# uCBoardBase.net
KiCad netlist of a schematic drawn in EAGLE
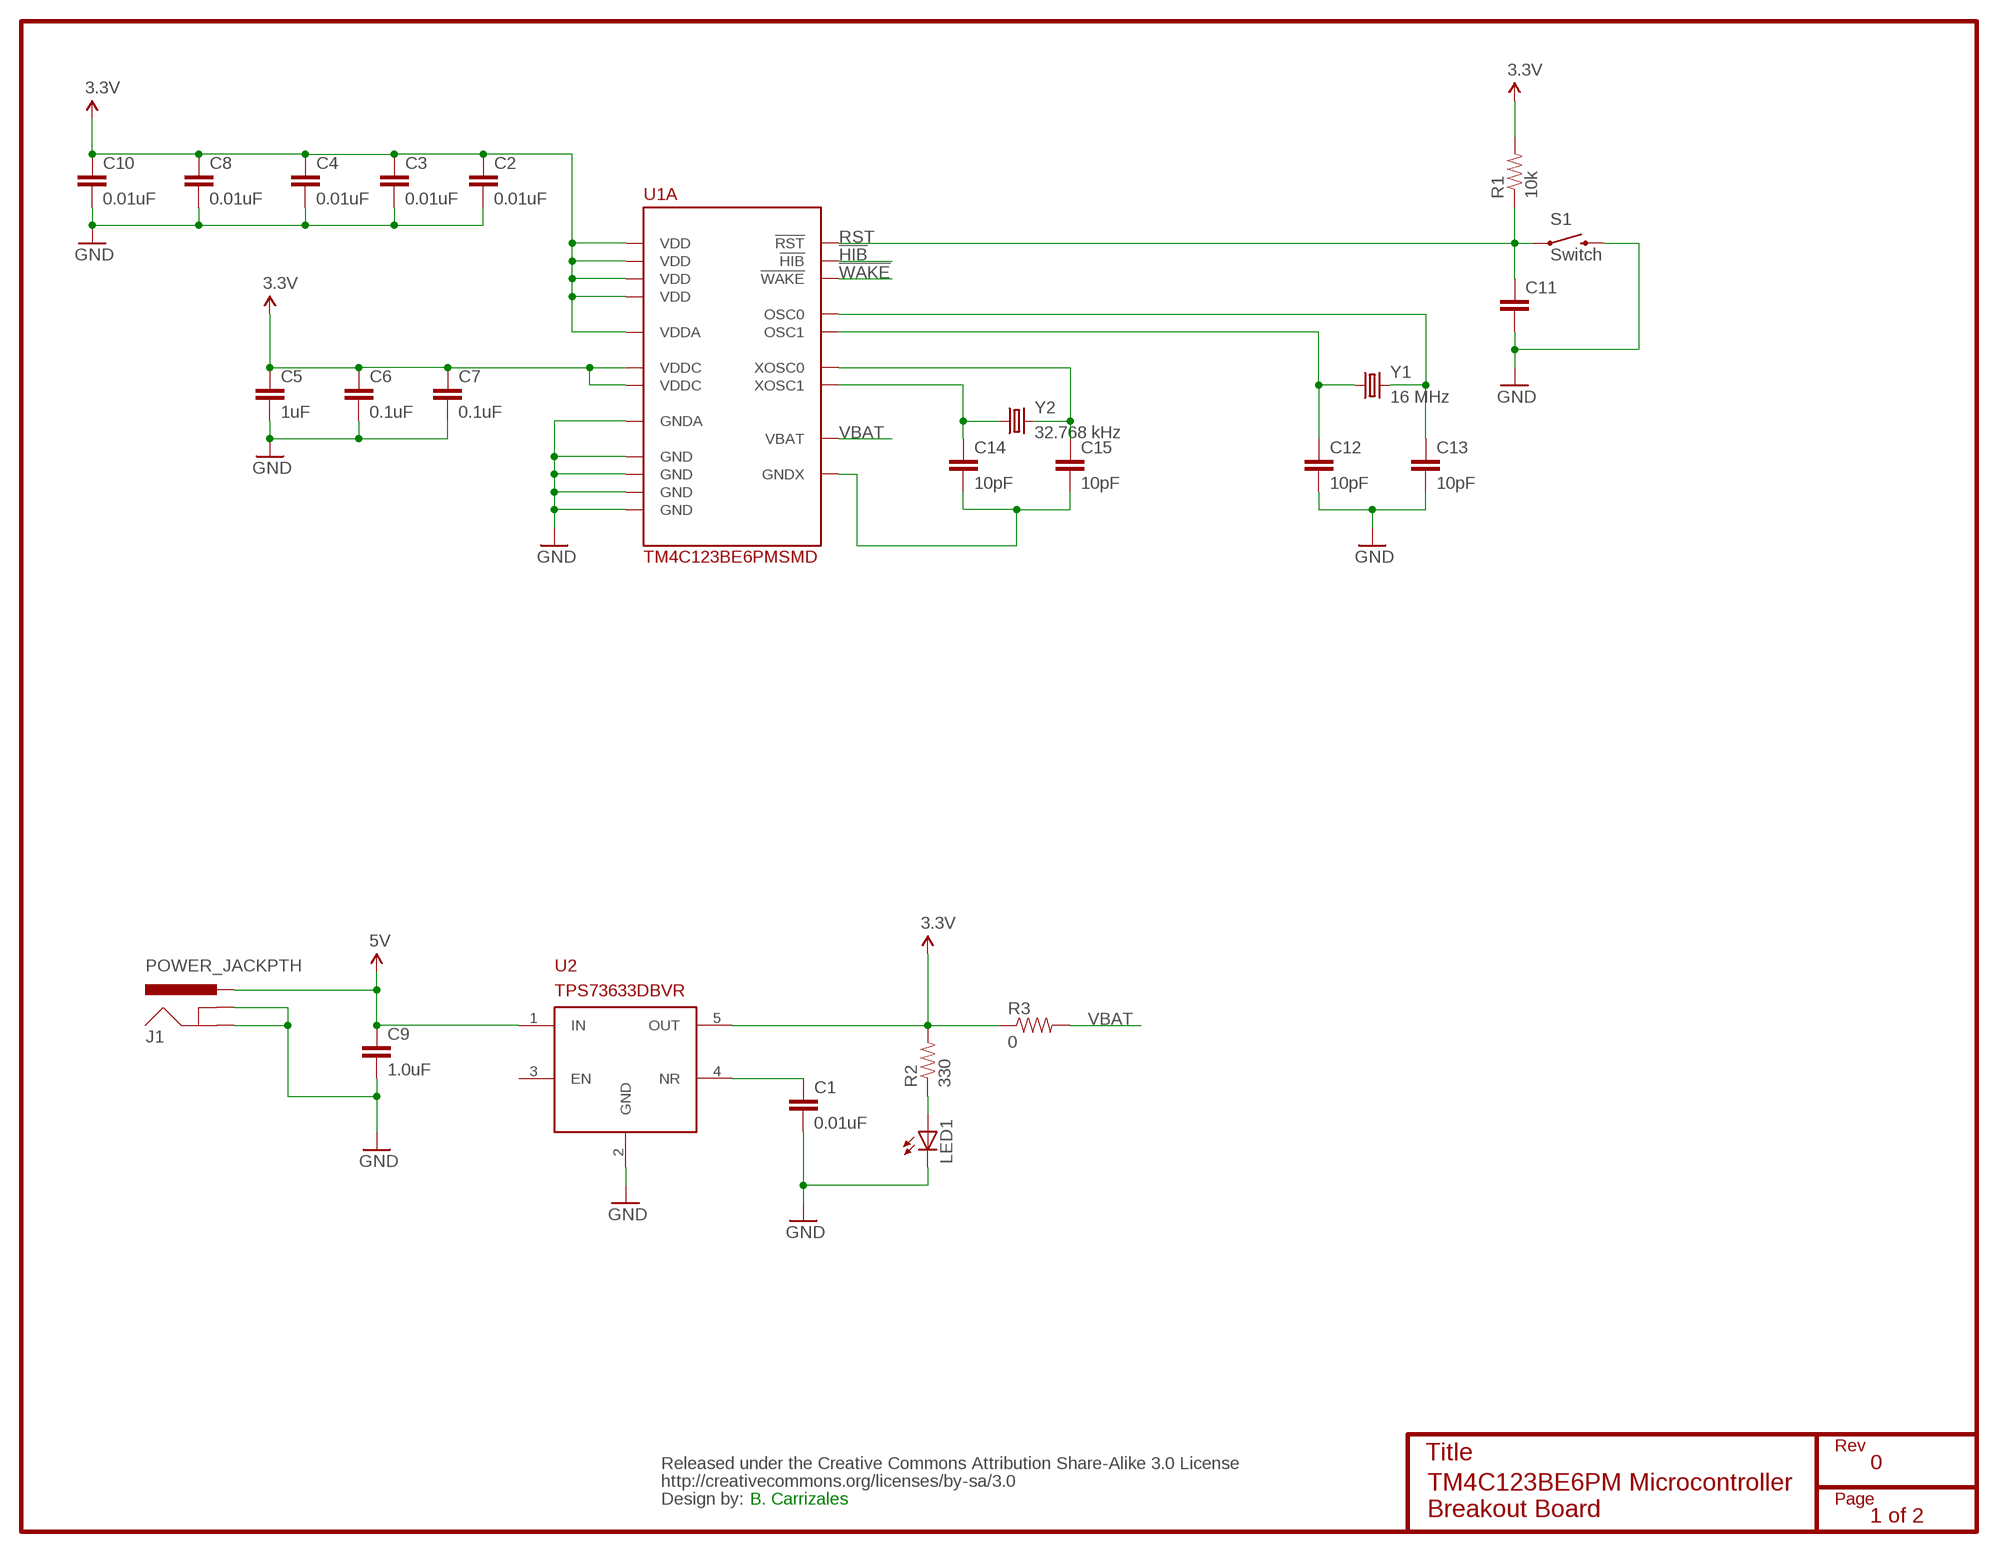
[diagram p0: schematic, sheet 1]
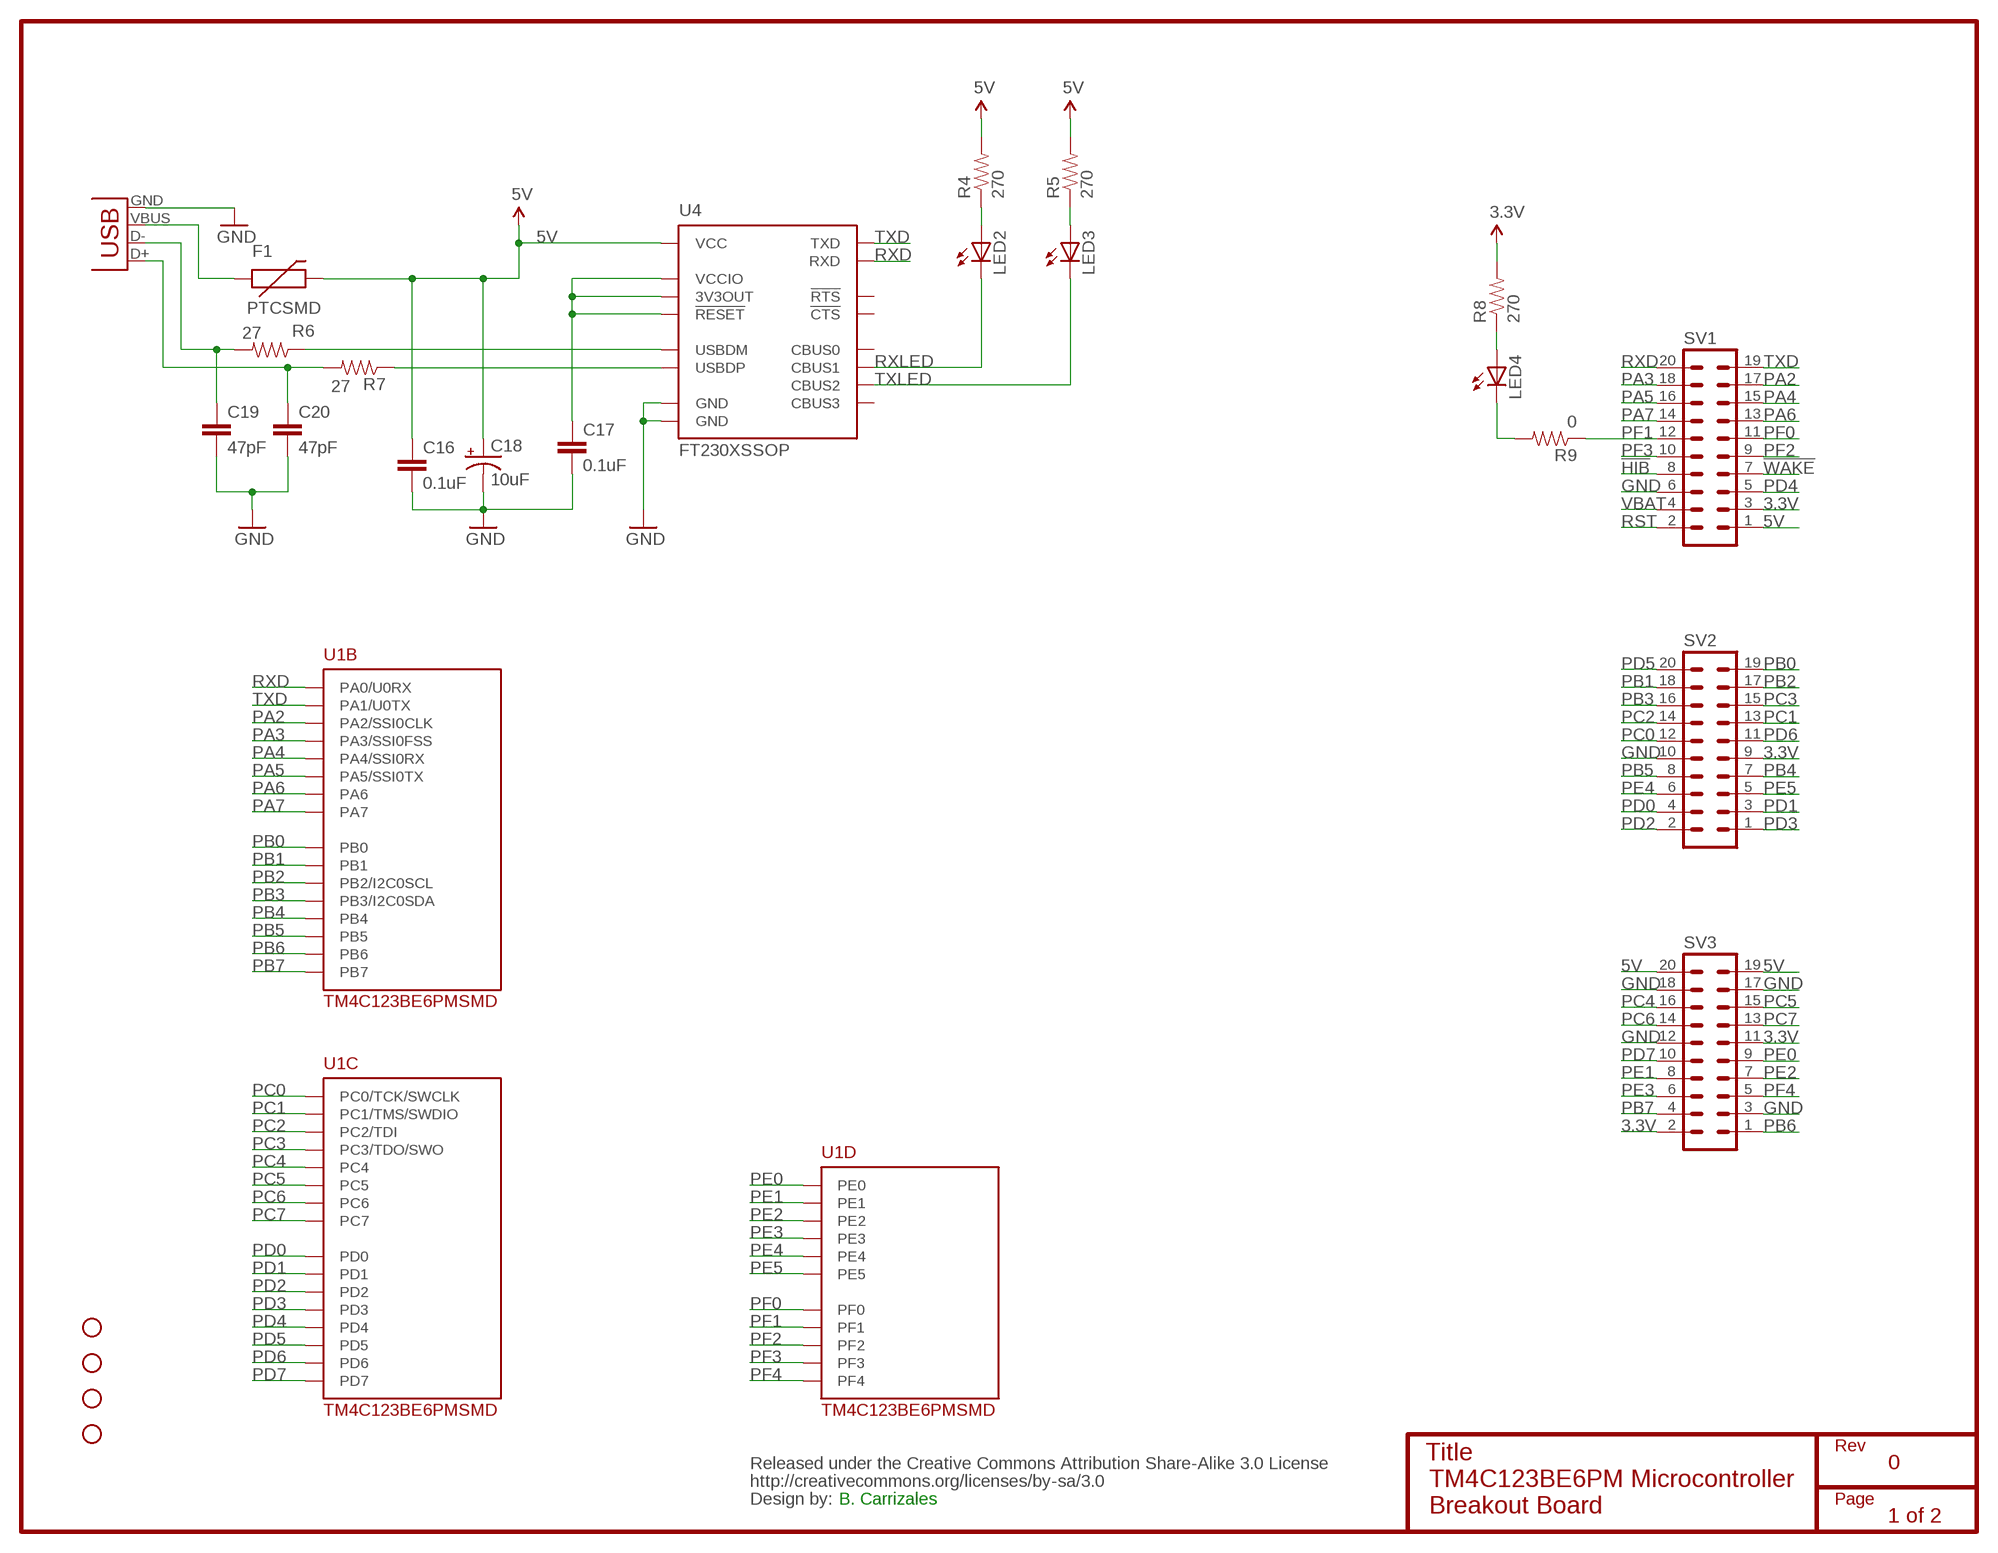
[diagram p1: schematic, sheet 2]

(export (version "E")
  (design (tool "Eeschema 10.0.6"))
  (components
    (comp (ref "C1")
      (value "0.01uF")
      (footprint "eagle-import:0603-CAP")
      (libsource (lib "eagle-import") (part "CAP0603-CAP"))
    )
    (comp (ref "C2")
      (value "0.01uF")
      (footprint "eagle-import:0603-CAP")
      (libsource (lib "eagle-import") (part "CAP0603-CAP"))
    )
    (comp (ref "C3")
      (value "0.01uF")
      (footprint "eagle-import:0603-CAP")
      (libsource (lib "eagle-import") (part "CAP0603-CAP"))
    )
    (comp (ref "C4")
      (value "0.01uF")
      (footprint "eagle-import:0603-CAP")
      (libsource (lib "eagle-import") (part "CAP0603-CAP"))
    )
    (comp (ref "C5")
      (value "1uF")
      (footprint "eagle-import:0603-CAP")
      (libsource (lib "eagle-import") (part "CAP0603-CAP"))
    )
    (comp (ref "C6")
      (value "0.1uF")
      (footprint "eagle-import:0603-CAP")
      (libsource (lib "eagle-import") (part "CAP0603-CAP"))
    )
    (comp (ref "C7")
      (value "0.1uF")
      (footprint "eagle-import:0603-CAP")
      (libsource (lib "eagle-import") (part "CAP0603-CAP"))
    )
    (comp (ref "C8")
      (value "0.01uF")
      (footprint "eagle-import:0603-CAP")
      (libsource (lib "eagle-import") (part "CAP0603-CAP"))
    )
    (comp (ref "C9")
      (value "1.0uF")
      (footprint "eagle-import:0603-CAP")
      (libsource (lib "eagle-import") (part "CAP0603-CAP"))
    )
    (comp (ref "C10")
      (value "0.01uF")
      (footprint "eagle-import:0603-CAP")
      (libsource (lib "eagle-import") (part "CAP0603-CAP"))
    )
    (comp (ref "C11")
      (value "CAP0603-CAP")
      (footprint "eagle-import:0603-CAP")
      (libsource (lib "eagle-import") (part "CAP0603-CAP"))
    )
    (comp (ref "C12")
      (value "10pF")
      (footprint "eagle-import:0603-CAP")
      (libsource (lib "eagle-import") (part "CAP0603-CAP"))
    )
    (comp (ref "C13")
      (value "10pF")
      (footprint "eagle-import:0603-CAP")
      (libsource (lib "eagle-import") (part "CAP0603-CAP"))
    )
    (comp (ref "C14")
      (value "10pF")
      (footprint "eagle-import:0603-CAP")
      (libsource (lib "eagle-import") (part "CAP0603-CAP"))
    )
    (comp (ref "C15")
      (value "10pF")
      (footprint "eagle-import:0603-CAP")
      (libsource (lib "eagle-import") (part "CAP0603-CAP"))
    )
    (comp (ref "CC_TEXT1")
      (value "CREATIVE_COMMONS")
      (footprint "eagle-import:CREATIVE_COMMONS")
      (libsource (lib "eagle-import") (part "CREATIVE_COMMONS"))
    )
    (comp (ref "J1")
      (value "POWER_JACKPTH")
      (footprint "eagle-import:POWER_JACK_PTH")
      (libsource (lib "eagle-import") (part "POWER_JACKPTH"))
    )
    (comp (ref "LED1")
      (value "LED1206")
      (footprint "eagle-import:LED-1206")
      (libsource (lib "eagle-import") (part "LED1206"))
    )
    (comp (ref "R1")
      (value "10k")
      (footprint "eagle-import:0603-RES")
      (libsource (lib "eagle-import") (part "RESISTOR0603-RES"))
    )
    (comp (ref "R2")
      (value "330")
      (footprint "eagle-import:0603-RES")
      (libsource (lib "eagle-import") (part "RESISTOR0603-RES"))
    )
    (comp (ref "R3")
      (value "0")
      (footprint "eagle-import:0603-RES")
      (libsource (lib "eagle-import") (part "RESISTOR0603-RES"))
    )
    (comp (ref "S1")
      (value "Switch")
      (footprint "eagle-import:TACTILE-SWITCH-1101NE")
      (libsource (lib "eagle-import") (part "SWITCH-MOMENTARY-2-SMD-1101NE"))
    )
    (comp (ref "U1")
      (value "TM4C123BE6PMSMD")
      (footprint "eagle-import:64LQFP")
      (fields (field (name "DIGIKEYPART#") "296-35834-ND"))
      (libsource (lib "eagle-import") (part "TM4C123BE6PMSMD"))
    )
    (comp (ref "U2")
      (value "TPS73633DBVR")
      (footprint "eagle-import:SOT23-DBV")
      (libsource (lib "eagle-import") (part "TPS73633DBVR"))
    )
    (comp (ref "Y1")
      (value "16 MHz")
      (footprint "eagle-import:HC49US")
      (libsource (lib "eagle-import") (part "CRYSTALHC49US"))
    )
    (comp (ref "Y2")
      (value "32.768 kHz")
      (footprint "eagle-import:TC26H")
      (libsource (lib "eagle-import") (part "CRYSTALTC26H"))
    )
    (comp (ref "C16")
      (value "0.1uF")
      (footprint "eagle-import:0603-CAP")
      (libsource (lib "eagle-import") (part "CAP0603-CAP"))
    )
    (comp (ref "C17")
      (value "0.1uF")
      (footprint "eagle-import:0603-CAP")
      (libsource (lib "eagle-import") (part "CAP0603-CAP"))
    )
    (comp (ref "C18")
      (value "10uF")
      (footprint "eagle-import:EIA3216-KIT")
      (libsource (lib "eagle-import") (part "CAP_POL1206-KIT"))
    )
    (comp (ref "C19")
      (value "47pF")
      (footprint "eagle-import:0603-CAP")
      (libsource (lib "eagle-import") (part "CAP0603-CAP"))
    )
    (comp (ref "C20")
      (value "47pF")
      (footprint "eagle-import:0603-CAP")
      (libsource (lib "eagle-import") (part "CAP0603-CAP"))
    )
    (comp (ref "CC_TEXT2")
      (value "CREATIVE_COMMONS")
      (footprint "eagle-import:CREATIVE_COMMONS")
      (libsource (lib "eagle-import") (part "CREATIVE_COMMONS"))
    )
    (comp (ref "F1")
      (value "PTCSMD")
      (footprint "eagle-import:PTC-1206")
      (libsource (lib "eagle-import") (part "PTCSMD"))
    )
    (comp (ref "JP2")
      (value "USBSMD")
      (footprint "eagle-import:USB-MINIB")
      (libsource (lib "eagle-import") (part "USBSMD"))
    )
    (comp (ref "LED2")
      (value "LED0603")
      (footprint "eagle-import:LED-0603")
      (libsource (lib "eagle-import") (part "LED0603"))
    )
    (comp (ref "LED3")
      (value "LED0603")
      (footprint "eagle-import:LED-0603")
      (libsource (lib "eagle-import") (part "LED0603"))
    )
    (comp (ref "LED4")
      (value "LED0603")
      (footprint "eagle-import:LED-0603")
      (libsource (lib "eagle-import") (part "LED0603"))
    )
    (comp (ref "R4")
      (value "270")
      (footprint "eagle-import:0603-RES")
      (libsource (lib "eagle-import") (part "RESISTOR0603-RES"))
    )
    (comp (ref "R5")
      (value "270")
      (footprint "eagle-import:0603-RES")
      (libsource (lib "eagle-import") (part "RESISTOR0603-RES"))
    )
    (comp (ref "R6")
      (value "27")
      (footprint "eagle-import:0603-RES")
      (libsource (lib "eagle-import") (part "RESISTOR0603-RES"))
    )
    (comp (ref "R7")
      (value "27")
      (footprint "eagle-import:0603-RES")
      (libsource (lib "eagle-import") (part "RESISTOR0603-RES"))
    )
    (comp (ref "R8")
      (value "270")
      (footprint "eagle-import:0603-RES")
      (libsource (lib "eagle-import") (part "RESISTOR0603-RES"))
    )
    (comp (ref "R9")
      (value "0")
      (footprint "eagle-import:0603-RES")
      (libsource (lib "eagle-import") (part "RESISTOR0603-RES"))
    )
    (comp (ref "STANDOFF1")
      (value "STAND-OFF")
      (footprint "eagle-import:STAND-OFF")
      (libsource (lib "eagle-import") (part "STAND-OFF"))
    )
    (comp (ref "STANDOFF2")
      (value "STAND-OFF")
      (footprint "eagle-import:STAND-OFF")
      (libsource (lib "eagle-import") (part "STAND-OFF"))
    )
    (comp (ref "STANDOFF3")
      (value "STAND-OFF")
      (footprint "eagle-import:STAND-OFF")
      (libsource (lib "eagle-import") (part "STAND-OFF"))
    )
    (comp (ref "STANDOFF4")
      (value "STAND-OFF")
      (footprint "eagle-import:STAND-OFF")
      (libsource (lib "eagle-import") (part "STAND-OFF"))
    )
    (comp (ref "SV1")
      (value "MA10-2")
      (footprint "eagle-import:MA10-2")
      (libsource (lib "eagle-import") (part "MA10-2"))
    )
    (comp (ref "SV2")
      (value "MA10-2")
      (footprint "eagle-import:MA10-2")
      (libsource (lib "eagle-import") (part "MA10-2"))
    )
    (comp (ref "SV3")
      (value "MA10-2")
      (footprint "eagle-import:MA10-2")
      (libsource (lib "eagle-import") (part "MA10-2"))
    )
    (comp (ref "U4")
      (value "FT230XSSOP")
      (footprint "eagle-import:SSOP16")
      (libsource (lib "eagle-import") (part "FT230XSSOP"))
    )
  )
  (nets
    (net (code "1") (name "3.3V") (class "Default")
      (node (ref "C10") (pin "1") (pinfunction "1_1") (pintype "passive"))
      (node (ref "C2") (pin "1") (pinfunction "1_1") (pintype "passive"))
      (node (ref "C3") (pin "1") (pinfunction "1_1") (pintype "passive"))
      (node (ref "C4") (pin "1") (pinfunction "1_1") (pintype "passive"))
      (node (ref "C5") (pin "1") (pinfunction "1_1") (pintype "passive"))
      (node (ref "C6") (pin "1") (pinfunction "1_1") (pintype "passive"))
      (node (ref "C7") (pin "1") (pinfunction "1_1") (pintype "passive"))
      (node (ref "C8") (pin "1") (pinfunction "1_1") (pintype "passive"))
      (node (ref "R1") (pin "2") (pinfunction "2_2") (pintype "passive"))
      (node (ref "R2") (pin "2") (pinfunction "2_2") (pintype "passive"))
      (node (ref "R3") (pin "1") (pinfunction "1_1") (pintype "passive"))
      (node (ref "R8") (pin "2") (pinfunction "2_2") (pintype "passive"))
      (node (ref "SV1") (pin "3") (pinfunction "3_3") (pintype "passive"))
      (node (ref "SV2") (pin "9") (pinfunction "9_9") (pintype "passive"))
      (node (ref "SV3") (pin "11") (pinfunction "11_11") (pintype "passive"))
      (node (ref "SV3") (pin "2") (pinfunction "2_2") (pintype "passive"))
      (node (ref "U1") (pin "11") (pinfunction "VDD_11") (pintype "power_in"))
      (node (ref "U1") (pin "2") (pinfunction "VDDA_2") (pintype "power_in"))
      (node (ref "U1") (pin "25") (pinfunction "VDDC_25") (pintype "power_in"))
      (node (ref "U1") (pin "26") (pinfunction "VDD_26") (pintype "power_in"))
      (node (ref "U1") (pin "42") (pinfunction "VDD_42") (pintype "power_in"))
      (node (ref "U1") (pin "54") (pinfunction "VDD_54") (pintype "power_in"))
      (node (ref "U1") (pin "56") (pinfunction "VDDC_56") (pintype "power_in"))
      (node (ref "U2") (pin "5") (pinfunction "OUT_5") (pintype "bidirectional"))
    )
    (net (code "2") (name "5V") (class "Default")
      (node (ref "C16") (pin "1") (pinfunction "1_1") (pintype "passive"))
      (node (ref "C18") (pin "A") (pinfunction "+_A") (pintype "passive"))
      (node (ref "C9") (pin "1") (pinfunction "1_1") (pintype "passive"))
      (node (ref "F1") (pin "2") (pinfunction "2_2") (pintype "bidirectional"))
      (node (ref "J1") (pin "PWR") (pinfunction "PWR_PWR") (pintype "bidirectional"))
      (node (ref "R4") (pin "2") (pinfunction "2_2") (pintype "passive"))
      (node (ref "R5") (pin "2") (pinfunction "2_2") (pintype "passive"))
      (node (ref "SV1") (pin "1") (pinfunction "1_1") (pintype "passive"))
      (node (ref "SV3") (pin "19") (pinfunction "19_19") (pintype "passive"))
      (node (ref "SV3") (pin "20") (pinfunction "20_20") (pintype "passive"))
      (node (ref "U2") (pin "1") (pinfunction "IN_1") (pintype "bidirectional"))
      (node (ref "U4") (pin "12") (pinfunction "VCC_12") (pintype "power_in"))
    )
    (net (code "3") (name "GND") (class "Default")
      (node (ref "C1") (pin "2") (pinfunction "2_2") (pintype "passive"))
      (node (ref "C10") (pin "2") (pinfunction "2_2") (pintype "passive"))
      (node (ref "C11") (pin "2") (pinfunction "2_2") (pintype "passive"))
      (node (ref "C12") (pin "2") (pinfunction "2_2") (pintype "passive"))
      (node (ref "C13") (pin "2") (pinfunction "2_2") (pintype "passive"))
      (node (ref "C16") (pin "2") (pinfunction "2_2") (pintype "passive"))
      (node (ref "C17") (pin "2") (pinfunction "2_2") (pintype "passive"))
      (node (ref "C18") (pin "C") (pinfunction "-_C") (pintype "passive"))
      (node (ref "C19") (pin "2") (pinfunction "2_2") (pintype "passive"))
      (node (ref "C2") (pin "2") (pinfunction "2_2") (pintype "passive"))
      (node (ref "C20") (pin "2") (pinfunction "2_2") (pintype "passive"))
      (node (ref "C3") (pin "2") (pinfunction "2_2") (pintype "passive"))
      (node (ref "C4") (pin "2") (pinfunction "2_2") (pintype "passive"))
      (node (ref "C5") (pin "2") (pinfunction "2_2") (pintype "passive"))
      (node (ref "C6") (pin "2") (pinfunction "2_2") (pintype "passive"))
      (node (ref "C7") (pin "2") (pinfunction "2_2") (pintype "passive"))
      (node (ref "C8") (pin "2") (pinfunction "2_2") (pintype "passive"))
      (node (ref "C9") (pin "2") (pinfunction "2_2") (pintype "passive"))
      (node (ref "J1") (pin "GND") (pinfunction "GND_GND") (pintype "bidirectional"))
      (node (ref "J1") (pin "GNDBREAK") (pinfunction "GNDBREAK_GNDBREAK") (pintype "bidirectional"))
      (node (ref "JP2") (pin "GND") (pinfunction "GND_GND") (pintype "bidirectional"))
      (node (ref "LED1") (pin "C") (pinfunction "C_C") (pintype "passive"))
      (node (ref "S1") (pin "P$2") (pinfunction "2_P$2") (pintype "passive"))
      (node (ref "SV1") (pin "6") (pinfunction "6_6") (pintype "passive"))
      (node (ref "SV2") (pin "10") (pinfunction "10_10") (pintype "passive"))
      (node (ref "SV3") (pin "12") (pinfunction "12_12") (pintype "passive"))
      (node (ref "SV3") (pin "17") (pinfunction "17_17") (pintype "passive"))
      (node (ref "SV3") (pin "18") (pinfunction "18_18") (pintype "passive"))
      (node (ref "SV3") (pin "3") (pinfunction "3_3") (pintype "passive"))
      (node (ref "U1") (pin "12") (pinfunction "GND_12") (pintype "power_in"))
      (node (ref "U1") (pin "27") (pinfunction "GND_27") (pintype "power_in"))
      (node (ref "U1") (pin "3") (pinfunction "GNDA_3") (pintype "power_in"))
      (node (ref "U1") (pin "39") (pinfunction "GND_39") (pintype "power_in"))
      (node (ref "U1") (pin "55") (pinfunction "GND_55") (pintype "power_in"))
      (node (ref "U2") (pin "2") (pinfunction "GND_2") (pintype "bidirectional"))
      (node (ref "U4") (pin "13") (pinfunction "GND_13") (pintype "power_in"))
      (node (ref "U4") (pin "5") (pinfunction "GND_5") (pintype "power_in"))
    )
    (net (code "4") (name "Net-(C19-Pad1)") (class "Default")
      (node (ref "C19") (pin "1") (pinfunction "1_1") (pintype "passive"))
      (node (ref "JP2") (pin "D-") (pinfunction "D-_D-") (pintype "bidirectional"))
      (node (ref "R6") (pin "2") (pinfunction "2_2") (pintype "passive"))
    )
    (net (code "5") (name "Net-(C20-Pad1)") (class "Default")
      (node (ref "C20") (pin "1") (pinfunction "1_1") (pintype "passive"))
      (node (ref "JP2") (pin "D+") (pinfunction "D+_D+") (pintype "bidirectional"))
      (node (ref "R7") (pin "2") (pinfunction "2_2") (pintype "passive"))
    )
    (net (code "6") (name "Net-(F1-Pad1)") (class "Default")
      (node (ref "F1") (pin "1") (pinfunction "1_1") (pintype "bidirectional"))
      (node (ref "JP2") (pin "VBUS") (pinfunction "VBUS_VBUS") (pintype "bidirectional"))
    )
    (net (code "7") (name "Net-(LED1-PadA)") (class "Default")
      (node (ref "LED1") (pin "A") (pinfunction "A_A") (pintype "passive"))
      (node (ref "R2") (pin "1") (pinfunction "1_1") (pintype "passive"))
    )
    (net (code "8") (name "Net-(LED2-PadA)") (class "Default")
      (node (ref "LED2") (pin "A") (pinfunction "A_A") (pintype "passive"))
      (node (ref "R4") (pin "1") (pinfunction "1_1") (pintype "passive"))
    )
    (net (code "9") (name "Net-(LED3-PadA)") (class "Default")
      (node (ref "LED3") (pin "A") (pinfunction "A_A") (pintype "passive"))
      (node (ref "R5") (pin "1") (pinfunction "1_1") (pintype "passive"))
    )
    (net (code "10") (name "Net-(LED4-PadA)") (class "Default")
      (node (ref "LED4") (pin "A") (pinfunction "A_A") (pintype "passive"))
      (node (ref "R8") (pin "1") (pinfunction "1_1") (pintype "passive"))
    )
    (net (code "11") (name "Net-(LED4-PadC)") (class "Default")
      (node (ref "LED4") (pin "C") (pinfunction "C_C") (pintype "passive"))
      (node (ref "R9") (pin "2") (pinfunction "2_2") (pintype "passive"))
    )
    (net (code "12") (name "Net-(U1A-GNDX)") (class "Default")
      (node (ref "C14") (pin "2") (pinfunction "2_2") (pintype "passive"))
      (node (ref "C15") (pin "2") (pinfunction "2_2") (pintype "passive"))
      (node (ref "U1") (pin "35") (pinfunction "GNDX_35") (pintype "power_in"))
    )
    (net (code "13") (name "Net-(U1A-OSC0)") (class "Default")
      (node (ref "C13") (pin "1") (pinfunction "1_1") (pintype "passive"))
      (node (ref "U1") (pin "40") (pinfunction "OSC0_40") (pintype "input"))
      (node (ref "Y1") (pin "2") (pinfunction "2_2") (pintype "passive"))
    )
    (net (code "14") (name "Net-(U1A-OSC1)") (class "Default")
      (node (ref "C12") (pin "1") (pinfunction "1_1") (pintype "passive"))
      (node (ref "U1") (pin "41") (pinfunction "OSC1_41") (pintype "output"))
      (node (ref "Y1") (pin "1") (pinfunction "1_1") (pintype "passive"))
    )
    (net (code "15") (name "Net-(U1A-XOSC0)") (class "Default")
      (node (ref "C15") (pin "1") (pinfunction "1_1") (pintype "passive"))
      (node (ref "U1") (pin "34") (pinfunction "XOSC0_34") (pintype "input"))
      (node (ref "Y2") (pin "2") (pinfunction "2_2") (pintype "passive"))
    )
    (net (code "16") (name "Net-(U1A-XOSC1)") (class "Default")
      (node (ref "C14") (pin "1") (pinfunction "1_1") (pintype "passive"))
      (node (ref "U1") (pin "36") (pinfunction "XOSC1_36") (pintype "output"))
      (node (ref "Y2") (pin "1") (pinfunction "1_1") (pintype "passive"))
    )
    (net (code "17") (name "Net-(U2-NR)") (class "Default")
      (node (ref "C1") (pin "1") (pinfunction "1_1") (pintype "passive"))
      (node (ref "U2") (pin "4") (pinfunction "NR_4") (pintype "bidirectional"))
    )
    (net (code "18") (name "Net-(U4-3V3OUT)") (class "Default")
      (node (ref "C17") (pin "1") (pinfunction "1_1") (pintype "passive"))
      (node (ref "U4") (pin "10") (pinfunction "3V3OUT_10") (pintype "power_in"))
      (node (ref "U4") (pin "11") (pinfunction "~{RESET}_11") (pintype "input"))
      (node (ref "U4") (pin "3") (pinfunction "VCCIO_3") (pintype "power_in"))
    )
    (net (code "19") (name "Net-(U4-USBDM)") (class "Default")
      (node (ref "R6") (pin "1") (pinfunction "1_1") (pintype "passive"))
      (node (ref "U4") (pin "9") (pinfunction "USBDM_9") (pintype "input"))
    )
    (net (code "20") (name "Net-(U4-USBDP)") (class "Default")
      (node (ref "R7") (pin "1") (pinfunction "1_1") (pintype "passive"))
      (node (ref "U4") (pin "8") (pinfunction "USBDP_8") (pintype "input"))
    )
    (net (code "21") (name "PA2") (class "Default")
      (node (ref "SV1") (pin "17") (pinfunction "17_17") (pintype "passive"))
      (node (ref "U1") (pin "19") (pinfunction "PA2/SSI0CLK_19") (pintype "bidirectional"))
    )
    (net (code "22") (name "PA3") (class "Default")
      (node (ref "SV1") (pin "18") (pinfunction "18_18") (pintype "passive"))
      (node (ref "U1") (pin "20") (pinfunction "PA3/SSI0FSS_20") (pintype "bidirectional"))
    )
    (net (code "23") (name "PA4") (class "Default")
      (node (ref "SV1") (pin "15") (pinfunction "15_15") (pintype "passive"))
      (node (ref "U1") (pin "21") (pinfunction "PA4/SSI0RX_21") (pintype "bidirectional"))
    )
    (net (code "24") (name "PA5") (class "Default")
      (node (ref "SV1") (pin "16") (pinfunction "16_16") (pintype "passive"))
      (node (ref "U1") (pin "22") (pinfunction "PA5/SSI0TX_22") (pintype "bidirectional"))
    )
    (net (code "25") (name "PA6") (class "Default")
      (node (ref "SV1") (pin "13") (pinfunction "13_13") (pintype "passive"))
      (node (ref "U1") (pin "23") (pinfunction "PA6_23") (pintype "bidirectional"))
    )
    (net (code "26") (name "PA7") (class "Default")
      (node (ref "SV1") (pin "14") (pinfunction "14_14") (pintype "passive"))
      (node (ref "U1") (pin "24") (pinfunction "PA7_24") (pintype "bidirectional"))
    )
    (net (code "27") (name "PB0") (class "Default")
      (node (ref "SV2") (pin "19") (pinfunction "19_19") (pintype "passive"))
      (node (ref "U1") (pin "45") (pinfunction "PB0_45") (pintype "bidirectional"))
    )
    (net (code "28") (name "PB1") (class "Default")
      (node (ref "SV2") (pin "18") (pinfunction "18_18") (pintype "passive"))
      (node (ref "U1") (pin "46") (pinfunction "PB1_46") (pintype "bidirectional"))
    )
    (net (code "29") (name "PB2") (class "Default")
      (node (ref "SV2") (pin "17") (pinfunction "17_17") (pintype "passive"))
      (node (ref "U1") (pin "47") (pinfunction "PB2/I2C0SCL_47") (pintype "bidirectional"))
    )
    (net (code "30") (name "PB3") (class "Default")
      (node (ref "SV2") (pin "16") (pinfunction "16_16") (pintype "passive"))
      (node (ref "U1") (pin "48") (pinfunction "PB3/I2C0SDA_48") (pintype "bidirectional"))
    )
    (net (code "31") (name "PB4") (class "Default")
      (node (ref "SV2") (pin "7") (pinfunction "7_7") (pintype "passive"))
      (node (ref "U1") (pin "58") (pinfunction "PB4_58") (pintype "bidirectional"))
    )
    (net (code "32") (name "PB5") (class "Default")
      (node (ref "SV2") (pin "8") (pinfunction "8_8") (pintype "passive"))
      (node (ref "U1") (pin "57") (pinfunction "PB5_57") (pintype "bidirectional"))
    )
    (net (code "33") (name "PB6") (class "Default")
      (node (ref "SV3") (pin "1") (pinfunction "1_1") (pintype "passive"))
      (node (ref "U1") (pin "1") (pinfunction "PB6_1") (pintype "bidirectional"))
    )
    (net (code "34") (name "PB7") (class "Default")
      (node (ref "SV3") (pin "4") (pinfunction "4_4") (pintype "passive"))
      (node (ref "U1") (pin "4") (pinfunction "PB7_4") (pintype "bidirectional"))
    )
    (net (code "35") (name "PC0") (class "Default")
      (node (ref "SV2") (pin "12") (pinfunction "12_12") (pintype "passive"))
      (node (ref "U1") (pin "52") (pinfunction "PC0/TCK/SWCLK_52") (pintype "bidirectional"))
    )
    (net (code "36") (name "PC1") (class "Default")
      (node (ref "SV2") (pin "13") (pinfunction "13_13") (pintype "passive"))
      (node (ref "U1") (pin "51") (pinfunction "PC1/TMS/SWDIO_51") (pintype "bidirectional"))
    )
    (net (code "37") (name "PC2") (class "Default")
      (node (ref "SV2") (pin "14") (pinfunction "14_14") (pintype "passive"))
      (node (ref "U1") (pin "50") (pinfunction "PC2/TDI_50") (pintype "bidirectional"))
    )
    (net (code "38") (name "PC3") (class "Default")
      (node (ref "SV2") (pin "15") (pinfunction "15_15") (pintype "passive"))
      (node (ref "U1") (pin "49") (pinfunction "PC3/TDO/SWO_49") (pintype "bidirectional"))
    )
    (net (code "39") (name "PC4") (class "Default")
      (node (ref "SV3") (pin "16") (pinfunction "16_16") (pintype "passive"))
      (node (ref "U1") (pin "16") (pinfunction "PC4_16") (pintype "bidirectional"))
    )
    (net (code "40") (name "PC5") (class "Default")
      (node (ref "SV3") (pin "15") (pinfunction "15_15") (pintype "passive"))
      (node (ref "U1") (pin "15") (pinfunction "PC5_15") (pintype "bidirectional"))
    )
    (net (code "41") (name "PC6") (class "Default")
      (node (ref "SV3") (pin "14") (pinfunction "14_14") (pintype "passive"))
      (node (ref "U1") (pin "14") (pinfunction "PC6_14") (pintype "bidirectional"))
    )
    (net (code "42") (name "PC7") (class "Default")
      (node (ref "SV3") (pin "13") (pinfunction "13_13") (pintype "passive"))
      (node (ref "U1") (pin "13") (pinfunction "PC7_13") (pintype "bidirectional"))
    )
    (net (code "43") (name "PD0") (class "Default")
      (node (ref "SV2") (pin "4") (pinfunction "4_4") (pintype "passive"))
      (node (ref "U1") (pin "61") (pinfunction "PD0_61") (pintype "bidirectional"))
    )
    (net (code "44") (name "PD1") (class "Default")
      (node (ref "SV2") (pin "3") (pinfunction "3_3") (pintype "passive"))
      (node (ref "U1") (pin "62") (pinfunction "PD1_62") (pintype "bidirectional"))
    )
    (net (code "45") (name "PD2") (class "Default")
      (node (ref "SV2") (pin "2") (pinfunction "2_2") (pintype "passive"))
      (node (ref "U1") (pin "63") (pinfunction "PD2_63") (pintype "bidirectional"))
    )
    (net (code "46") (name "PD3") (class "Default")
      (node (ref "SV2") (pin "1") (pinfunction "1_1") (pintype "passive"))
      (node (ref "U1") (pin "64") (pinfunction "PD3_64") (pintype "bidirectional"))
    )
    (net (code "47") (name "PD4") (class "Default")
      (node (ref "SV1") (pin "5") (pinfunction "5_5") (pintype "passive"))
      (node (ref "U1") (pin "43") (pinfunction "PD4_43") (pintype "bidirectional"))
    )
    (net (code "48") (name "PD5") (class "Default")
      (node (ref "SV2") (pin "20") (pinfunction "20_20") (pintype "passive"))
      (node (ref "U1") (pin "44") (pinfunction "PD5_44") (pintype "bidirectional"))
    )
    (net (code "49") (name "PD6") (class "Default")
      (node (ref "SV2") (pin "11") (pinfunction "11_11") (pintype "passive"))
      (node (ref "U1") (pin "53") (pinfunction "PD6_53") (pintype "bidirectional"))
    )
    (net (code "50") (name "PD7") (class "Default")
      (node (ref "SV3") (pin "10") (pinfunction "10_10") (pintype "passive"))
      (node (ref "U1") (pin "10") (pinfunction "PD7_10") (pintype "bidirectional"))
    )
    (net (code "51") (name "PE0") (class "Default")
      (node (ref "SV3") (pin "9") (pinfunction "9_9") (pintype "passive"))
      (node (ref "U1") (pin "9") (pinfunction "PE0_9") (pintype "bidirectional"))
    )
    (net (code "52") (name "PE1") (class "Default")
      (node (ref "SV3") (pin "8") (pinfunction "8_8") (pintype "passive"))
      (node (ref "U1") (pin "8") (pinfunction "PE1_8") (pintype "bidirectional"))
    )
    (net (code "53") (name "PE2") (class "Default")
      (node (ref "SV3") (pin "7") (pinfunction "7_7") (pintype "passive"))
      (node (ref "U1") (pin "7") (pinfunction "PE2_7") (pintype "bidirectional"))
    )
    (net (code "54") (name "PE3") (class "Default")
      (node (ref "SV3") (pin "6") (pinfunction "6_6") (pintype "passive"))
      (node (ref "U1") (pin "6") (pinfunction "PE3_6") (pintype "bidirectional"))
    )
    (net (code "55") (name "PE4") (class "Default")
      (node (ref "SV2") (pin "6") (pinfunction "6_6") (pintype "passive"))
      (node (ref "U1") (pin "59") (pinfunction "PE4_59") (pintype "bidirectional"))
    )
    (net (code "56") (name "PE5") (class "Default")
      (node (ref "SV2") (pin "5") (pinfunction "5_5") (pintype "passive"))
      (node (ref "U1") (pin "60") (pinfunction "PE5_60") (pintype "bidirectional"))
    )
    (net (code "57") (name "PF0") (class "Default")
      (node (ref "SV1") (pin "11") (pinfunction "11_11") (pintype "passive"))
      (node (ref "U1") (pin "28") (pinfunction "PF0_28") (pintype "bidirectional"))
    )
    (net (code "58") (name "PF1") (class "Default")
      (node (ref "R9") (pin "1") (pinfunction "1_1") (pintype "passive"))
      (node (ref "SV1") (pin "12") (pinfunction "12_12") (pintype "passive"))
      (node (ref "U1") (pin "29") (pinfunction "PF1_29") (pintype "bidirectional"))
    )
    (net (code "59") (name "PF2") (class "Default")
      (node (ref "SV1") (pin "9") (pinfunction "9_9") (pintype "passive"))
      (node (ref "U1") (pin "30") (pinfunction "PF2_30") (pintype "bidirectional"))
    )
    (net (code "60") (name "PF3") (class "Default")
      (node (ref "SV1") (pin "10") (pinfunction "10_10") (pintype "passive"))
      (node (ref "U1") (pin "31") (pinfunction "PF3_31") (pintype "bidirectional"))
    )
    (net (code "61") (name "PF4") (class "Default")
      (node (ref "SV3") (pin "5") (pinfunction "5_5") (pintype "passive"))
      (node (ref "U1") (pin "5") (pinfunction "PF4_5") (pintype "bidirectional"))
    )
    (net (code "62") (name "RST") (class "Default")
      (node (ref "C11") (pin "1") (pinfunction "1_1") (pintype "passive"))
      (node (ref "R1") (pin "1") (pinfunction "1_1") (pintype "passive"))
      (node (ref "S1") (pin "P$1") (pinfunction "1_P$1") (pintype "passive"))
      (node (ref "SV1") (pin "2") (pinfunction "2_2") (pintype "passive"))
      (node (ref "U1") (pin "38") (pinfunction "~{RST}_38") (pintype "input"))
    )
    (net (code "63") (name "RXD") (class "Default")
      (node (ref "SV1") (pin "20") (pinfunction "20_20") (pintype "passive"))
      (node (ref "U1") (pin "17") (pinfunction "PA0/U0RX_17") (pintype "bidirectional"))
      (node (ref "U4") (pin "4") (pinfunction "RXD_4") (pintype "input"))
    )
    (net (code "64") (name "RXLED") (class "Default")
      (node (ref "LED2") (pin "C") (pinfunction "C_C") (pintype "passive"))
      (node (ref "U4") (pin "14") (pinfunction "CBUS1_14") (pintype "bidirectional"))
    )
    (net (code "65") (name "TXD") (class "Default")
      (node (ref "SV1") (pin "19") (pinfunction "19_19") (pintype "passive"))
      (node (ref "U1") (pin "18") (pinfunction "PA1/U0TX_18") (pintype "bidirectional"))
      (node (ref "U4") (pin "1") (pinfunction "TXD_1") (pintype "output"))
    )
    (net (code "66") (name "TXLED") (class "Default")
      (node (ref "LED3") (pin "C") (pinfunction "C_C") (pintype "passive"))
      (node (ref "U4") (pin "7") (pinfunction "CBUS2_7") (pintype "bidirectional"))
    )
    (net (code "67") (name "VBAT") (class "Default")
      (node (ref "R3") (pin "2") (pinfunction "2_2") (pintype "passive"))
      (node (ref "SV1") (pin "4") (pinfunction "4_4") (pintype "passive"))
      (node (ref "U1") (pin "37") (pinfunction "VBAT_37") (pintype "power_in"))
    )
    (net (code "68") (name "unconnected-(U2-EN-Pad3)") (class "Default")
      (node (ref "U2") (pin "3") (pinfunction "EN_3") (pintype "bidirectional"))
    )
    (net (code "69") (name "unconnected-(U4-CBUS0-Pad15)") (class "Default")
      (node (ref "U4") (pin "15") (pinfunction "CBUS0_15") (pintype "bidirectional"))
    )
    (net (code "70") (name "unconnected-(U4-CBUS3-Pad16)") (class "Default")
      (node (ref "U4") (pin "16") (pinfunction "CBUS3_16") (pintype "bidirectional"))
    )
    (net (code "71") (name "unconnected-(U4-~{CTS}-Pad6)") (class "Default")
      (node (ref "U4") (pin "6") (pinfunction "~{CTS}_6") (pintype "input"))
    )
    (net (code "72") (name "unconnected-(U4-~{RTS}-Pad2)") (class "Default")
      (node (ref "U4") (pin "2") (pinfunction "~{RTS}_2") (pintype "output"))
    )
    (net (code "73") (name "~{HIB}") (class "Default")
      (node (ref "SV1") (pin "8") (pinfunction "8_8") (pintype "passive"))
      (node (ref "U1") (pin "33") (pinfunction "~{HIB}_33") (pintype "output"))
    )
    (net (code "74") (name "~{WAKE}") (class "Default")
      (node (ref "SV1") (pin "7") (pinfunction "7_7") (pintype "passive"))
      (node (ref "U1") (pin "32") (pinfunction "~{WAKE}_32") (pintype "input"))
    )
  )
)
